# lab4_v1.net
KiCad netlist of a schematic drawn in EAGLE
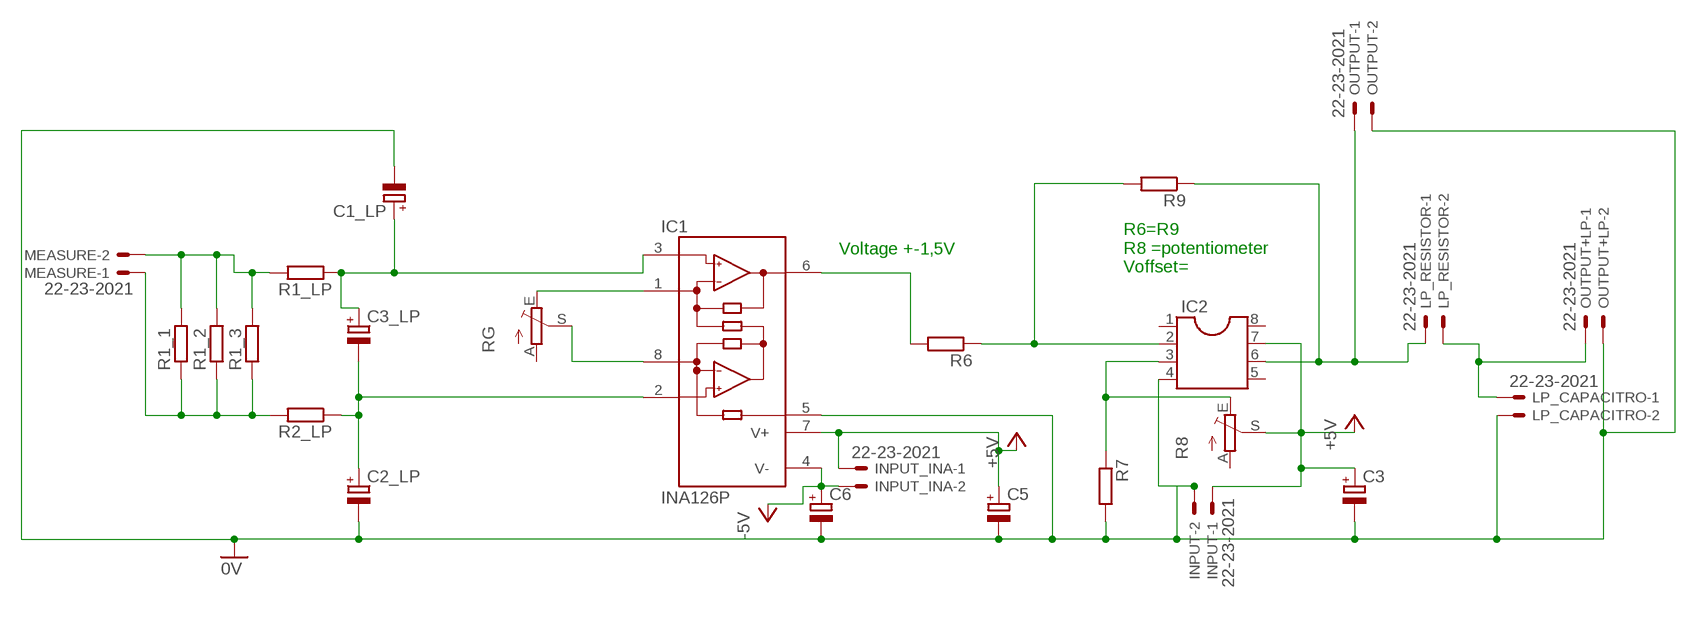
[diagram p0: schematic, sheet 1]

(export (version "E")
  (design (tool "Eeschema 10.0.6"))
  (components
    (comp (ref "C1_LP")
      (value "CPOL-EUE5-10.5")
      (footprint "eagle-import:E5-10,5")
      (libsource (lib "eagle-import") (part "CPOL-EUE5-10.5"))
    )
    (comp (ref "C2_LP")
      (value "CPOL-EUE5-10.5")
      (footprint "eagle-import:E5-10,5")
      (libsource (lib "eagle-import") (part "CPOL-EUE5-10.5"))
    )
    (comp (ref "C3")
      (value "CPOL-EUE5-10.5")
      (footprint "eagle-import:E5-10,5")
      (libsource (lib "eagle-import") (part "CPOL-EUE5-10.5"))
    )
    (comp (ref "C3_LP")
      (value "CPOL-EUE5-10.5")
      (footprint "eagle-import:E5-10,5")
      (libsource (lib "eagle-import") (part "CPOL-EUE5-10.5"))
    )
    (comp (ref "C5")
      (value "CPOL-EUE5-10.5")
      (footprint "eagle-import:E5-10,5")
      (libsource (lib "eagle-import") (part "CPOL-EUE5-10.5"))
    )
    (comp (ref "C6")
      (value "CPOL-EUE5-10.5")
      (footprint "eagle-import:E5-10,5")
      (libsource (lib "eagle-import") (part "CPOL-EUE5-10.5"))
    )
    (comp (ref "IC1")
      (value "INA126P")
      (footprint "eagle-import:DIL08")
      (fields (field (name "MF") "TEXAS INSTRUMENT CONNECTORS"))
      (libsource (lib "eagle-import") (part "INA126P"))
    )
    (comp (ref "IC2")
      (value "DIL8")
      (footprint "eagle-import:DIL08")
      (libsource (lib "eagle-import") (part "DIL8"))
    )
    (comp (ref "INPUT")
      (value "22-23-2021")
      (footprint "eagle-import:22-23-2021")
      (fields (field (name "MF") "MOLEX"))
      (libsource (lib "eagle-import") (part "22-23-2021"))
    )
    (comp (ref "INPUT_INA")
      (value "22-23-2021")
      (footprint "eagle-import:22-23-2021")
      (fields (field (name "MF") "MOLEX"))
      (libsource (lib "eagle-import") (part "22-23-2021"))
    )
    (comp (ref "LP_CAPACITRO")
      (value "22-23-2021")
      (footprint "eagle-import:22-23-2021")
      (fields (field (name "MF") "MOLEX"))
      (libsource (lib "eagle-import") (part "22-23-2021"))
    )
    (comp (ref "LP_RESISTOR")
      (value "22-23-2021")
      (footprint "eagle-import:22-23-2021")
      (fields (field (name "MF") "MOLEX"))
      (libsource (lib "eagle-import") (part "22-23-2021"))
    )
    (comp (ref "MEASURE")
      (value "22-23-2021")
      (footprint "eagle-import:22-23-2021")
      (fields (field (name "MF") "MOLEX"))
      (libsource (lib "eagle-import") (part "22-23-2021"))
    )
    (comp (ref "OUTPUT")
      (value "22-23-2021")
      (footprint "eagle-import:22-23-2021")
      (fields (field (name "MF") "MOLEX"))
      (libsource (lib "eagle-import") (part "22-23-2021"))
    )
    (comp (ref "OUTPUT+LP")
      (value "22-23-2021")
      (footprint "eagle-import:22-23-2021")
      (fields (field (name "MF") "MOLEX"))
      (libsource (lib "eagle-import") (part "22-23-2021"))
    )
    (comp (ref "R1_1")
      (value "R-EU_0617/22")
      (footprint "eagle-import:0617_22")
      (libsource (lib "eagle-import") (part "R-EU_0617/22"))
    )
    (comp (ref "R1_2")
      (value "R-EU_0617/22")
      (footprint "eagle-import:0617_22")
      (libsource (lib "eagle-import") (part "R-EU_0617/22"))
    )
    (comp (ref "R1_3")
      (value "R-EU_0617/22")
      (footprint "eagle-import:0617_22")
      (libsource (lib "eagle-import") (part "R-EU_0617/22"))
    )
    (comp (ref "R1_LP")
      (value "R-EU_0207/7")
      (footprint "eagle-import:0207_7")
      (libsource (lib "eagle-import") (part "R-EU_0207/7"))
    )
    (comp (ref "R2_LP")
      (value "R-EU_0207/7")
      (footprint "eagle-import:0207_7")
      (libsource (lib "eagle-import") (part "R-EU_0207/7"))
    )
    (comp (ref "R6")
      (value "R-EU_0207/7")
      (footprint "eagle-import:0207_7")
      (libsource (lib "eagle-import") (part "R-EU_0207/7"))
    )
    (comp (ref "R7")
      (value "R-EU_0207/7")
      (footprint "eagle-import:0207_7")
      (libsource (lib "eagle-import") (part "R-EU_0207/7"))
    )
    (comp (ref "R8")
      (value "TRIM_EU-B25P")
      (footprint "eagle-import:B25P")
      (libsource (lib "eagle-import") (part "TRIM_EU-B25P"))
    )
    (comp (ref "R9")
      (value "R-EU_0207/7")
      (footprint "eagle-import:0207_7")
      (libsource (lib "eagle-import") (part "R-EU_0207/7"))
    )
    (comp (ref "RG")
      (value "TRIM_EU-B25P")
      (footprint "eagle-import:B25P")
      (libsource (lib "eagle-import") (part "TRIM_EU-B25P"))
    )
  )
  (nets
    (net (code "1") (name "+5V") (class "Default")
      (node (ref "C3") (pin "+") (pinfunction "+_+") (pintype "passive"))
      (node (ref "C5") (pin "+") (pinfunction "+_+") (pintype "passive"))
      (node (ref "IC1") (pin "7") (pinfunction "V+_7") (pintype "power_in"))
      (node (ref "IC2") (pin "7") (pinfunction "7_7") (pintype "passive"))
      (node (ref "INPUT") (pin "1") (pinfunction "S_1") (pintype "passive"))
      (node (ref "INPUT_INA") (pin "1") (pinfunction "S_1") (pintype "passive"))
      (node (ref "R8") (pin "S") (pinfunction "S_S") (pintype "passive"))
    )
    (net (code "2") (name "-5V") (class "Default")
      (node (ref "C6") (pin "+") (pinfunction "+_+") (pintype "passive"))
      (node (ref "IC1") (pin "4") (pinfunction "V-_4") (pintype "power_in"))
      (node (ref "INPUT_INA") (pin "2") (pinfunction "S_2") (pintype "passive"))
    )
    (net (code "3") (name "0V") (class "Default")
      (node (ref "C1_LP") (pin "-") (pinfunction "-_-") (pintype "passive"))
      (node (ref "C2_LP") (pin "-") (pinfunction "-_-") (pintype "passive"))
      (node (ref "C3") (pin "-") (pinfunction "-_-") (pintype "passive"))
      (node (ref "C5") (pin "-") (pinfunction "-_-") (pintype "passive"))
      (node (ref "C6") (pin "-") (pinfunction "-_-") (pintype "passive"))
      (node (ref "IC1") (pin "5") (pinfunction "REF_5") (pintype "passive"))
      (node (ref "IC2") (pin "4") (pinfunction "4_4") (pintype "passive"))
      (node (ref "INPUT") (pin "2") (pinfunction "S_2") (pintype "passive"))
      (node (ref "LP_CAPACITRO") (pin "2") (pinfunction "S_2") (pintype "passive"))
      (node (ref "OUTPUT") (pin "2") (pinfunction "S_2") (pintype "passive"))
      (node (ref "OUTPUT+LP") (pin "2") (pinfunction "S_2") (pintype "passive"))
      (node (ref "R7") (pin "2") (pinfunction "2_2") (pintype "passive"))
    )
    (net (code "4") (name "Net-(IC1-+IN)") (class "Default")
      (node (ref "C1_LP") (pin "+") (pinfunction "+_+") (pintype "passive"))
      (node (ref "C3_LP") (pin "+") (pinfunction "+_+") (pintype "passive"))
      (node (ref "IC1") (pin "3") (pinfunction "+IN_3") (pintype "input"))
      (node (ref "R1_LP") (pin "1") (pinfunction "1_1") (pintype "passive"))
    )
    (net (code "5") (name "Net-(IC1--IN)") (class "Default")
      (node (ref "C2_LP") (pin "+") (pinfunction "+_+") (pintype "passive"))
      (node (ref "C3_LP") (pin "-") (pinfunction "-_-") (pintype "passive"))
      (node (ref "IC1") (pin "2") (pinfunction "-IN_2") (pintype "input"))
      (node (ref "R2_LP") (pin "1") (pinfunction "1_1") (pintype "passive"))
    )
    (net (code "6") (name "Net-(IC1-OUT)") (class "Default")
      (node (ref "IC1") (pin "6") (pinfunction "OUT_6") (pintype "output"))
      (node (ref "R6") (pin "2") (pinfunction "2_2") (pintype "passive"))
    )
    (net (code "7") (name "Net-(IC1-RG-Pad1)") (class "Default")
      (node (ref "IC1") (pin "1") (pinfunction "RG_1") (pintype "passive"))
      (node (ref "RG") (pin "E") (pinfunction "E_E") (pintype "passive"))
    )
    (net (code "8") (name "Net-(IC1-RG-Pad8)") (class "Default")
      (node (ref "IC1") (pin "8") (pinfunction "RG_8") (pintype "passive"))
      (node (ref "RG") (pin "S") (pinfunction "S_S") (pintype "passive"))
    )
    (net (code "9") (name "Net-(IC2-Pad2)") (class "Default")
      (node (ref "IC2") (pin "2") (pinfunction "2_2") (pintype "passive"))
      (node (ref "R6") (pin "1") (pinfunction "1_1") (pintype "passive"))
      (node (ref "R9") (pin "2") (pinfunction "2_2") (pintype "passive"))
    )
    (net (code "10") (name "Net-(IC2-Pad3)") (class "Default")
      (node (ref "IC2") (pin "3") (pinfunction "3_3") (pintype "passive"))
      (node (ref "R7") (pin "1") (pinfunction "1_1") (pintype "passive"))
      (node (ref "R8") (pin "E") (pinfunction "E_E") (pintype "passive"))
    )
    (net (code "11") (name "Net-(LP_CAPACITROA-S)") (class "Default")
      (node (ref "LP_CAPACITRO") (pin "1") (pinfunction "S_1") (pintype "passive"))
      (node (ref "LP_RESISTOR") (pin "2") (pinfunction "S_2") (pintype "passive"))
      (node (ref "OUTPUT+LP") (pin "1") (pinfunction "S_1") (pintype "passive"))
    )
    (net (code "12") (name "Net-(LP_RESISTORA-S)") (class "Default")
      (node (ref "IC2") (pin "6") (pinfunction "6_6") (pintype "passive"))
      (node (ref "LP_RESISTOR") (pin "1") (pinfunction "S_1") (pintype "passive"))
      (node (ref "OUTPUT") (pin "1") (pinfunction "S_1") (pintype "passive"))
      (node (ref "R9") (pin "1") (pinfunction "1_1") (pintype "passive"))
    )
    (net (code "13") (name "Net-(MEASUREA-S)") (class "Default")
      (node (ref "MEASURE") (pin "1") (pinfunction "S_1") (pintype "passive"))
      (node (ref "R1_1") (pin "1") (pinfunction "1_1") (pintype "passive"))
      (node (ref "R1_2") (pin "1") (pinfunction "1_1") (pintype "passive"))
      (node (ref "R1_3") (pin "1") (pinfunction "1_1") (pintype "passive"))
      (node (ref "R2_LP") (pin "2") (pinfunction "2_2") (pintype "passive"))
    )
    (net (code "14") (name "Net-(MEASUREB-S)") (class "Default")
      (node (ref "MEASURE") (pin "2") (pinfunction "S_2") (pintype "passive"))
      (node (ref "R1_1") (pin "2") (pinfunction "2_2") (pintype "passive"))
      (node (ref "R1_2") (pin "2") (pinfunction "2_2") (pintype "passive"))
      (node (ref "R1_3") (pin "2") (pinfunction "2_2") (pintype "passive"))
      (node (ref "R1_LP") (pin "2") (pinfunction "2_2") (pintype "passive"))
    )
    (net (code "15") (name "unconnected-(IC2-Pad1)") (class "Default")
      (node (ref "IC2") (pin "1") (pinfunction "1_1") (pintype "passive"))
    )
    (net (code "16") (name "unconnected-(IC2-Pad5)") (class "Default")
      (node (ref "IC2") (pin "5") (pinfunction "5_5") (pintype "passive"))
    )
    (net (code "17") (name "unconnected-(IC2-Pad8)") (class "Default")
      (node (ref "IC2") (pin "8") (pinfunction "8_8") (pintype "passive"))
    )
    (net (code "18") (name "unconnected-(R8-PadA)") (class "Default")
      (node (ref "R8") (pin "A") (pinfunction "A_A") (pintype "passive"))
    )
    (net (code "19") (name "unconnected-(RG-PadA)") (class "Default")
      (node (ref "RG") (pin "A") (pinfunction "A_A") (pintype "passive"))
    )
  )
)
